# Notification_area.net
KiCad netlist of a schematic drawn in EAGLE
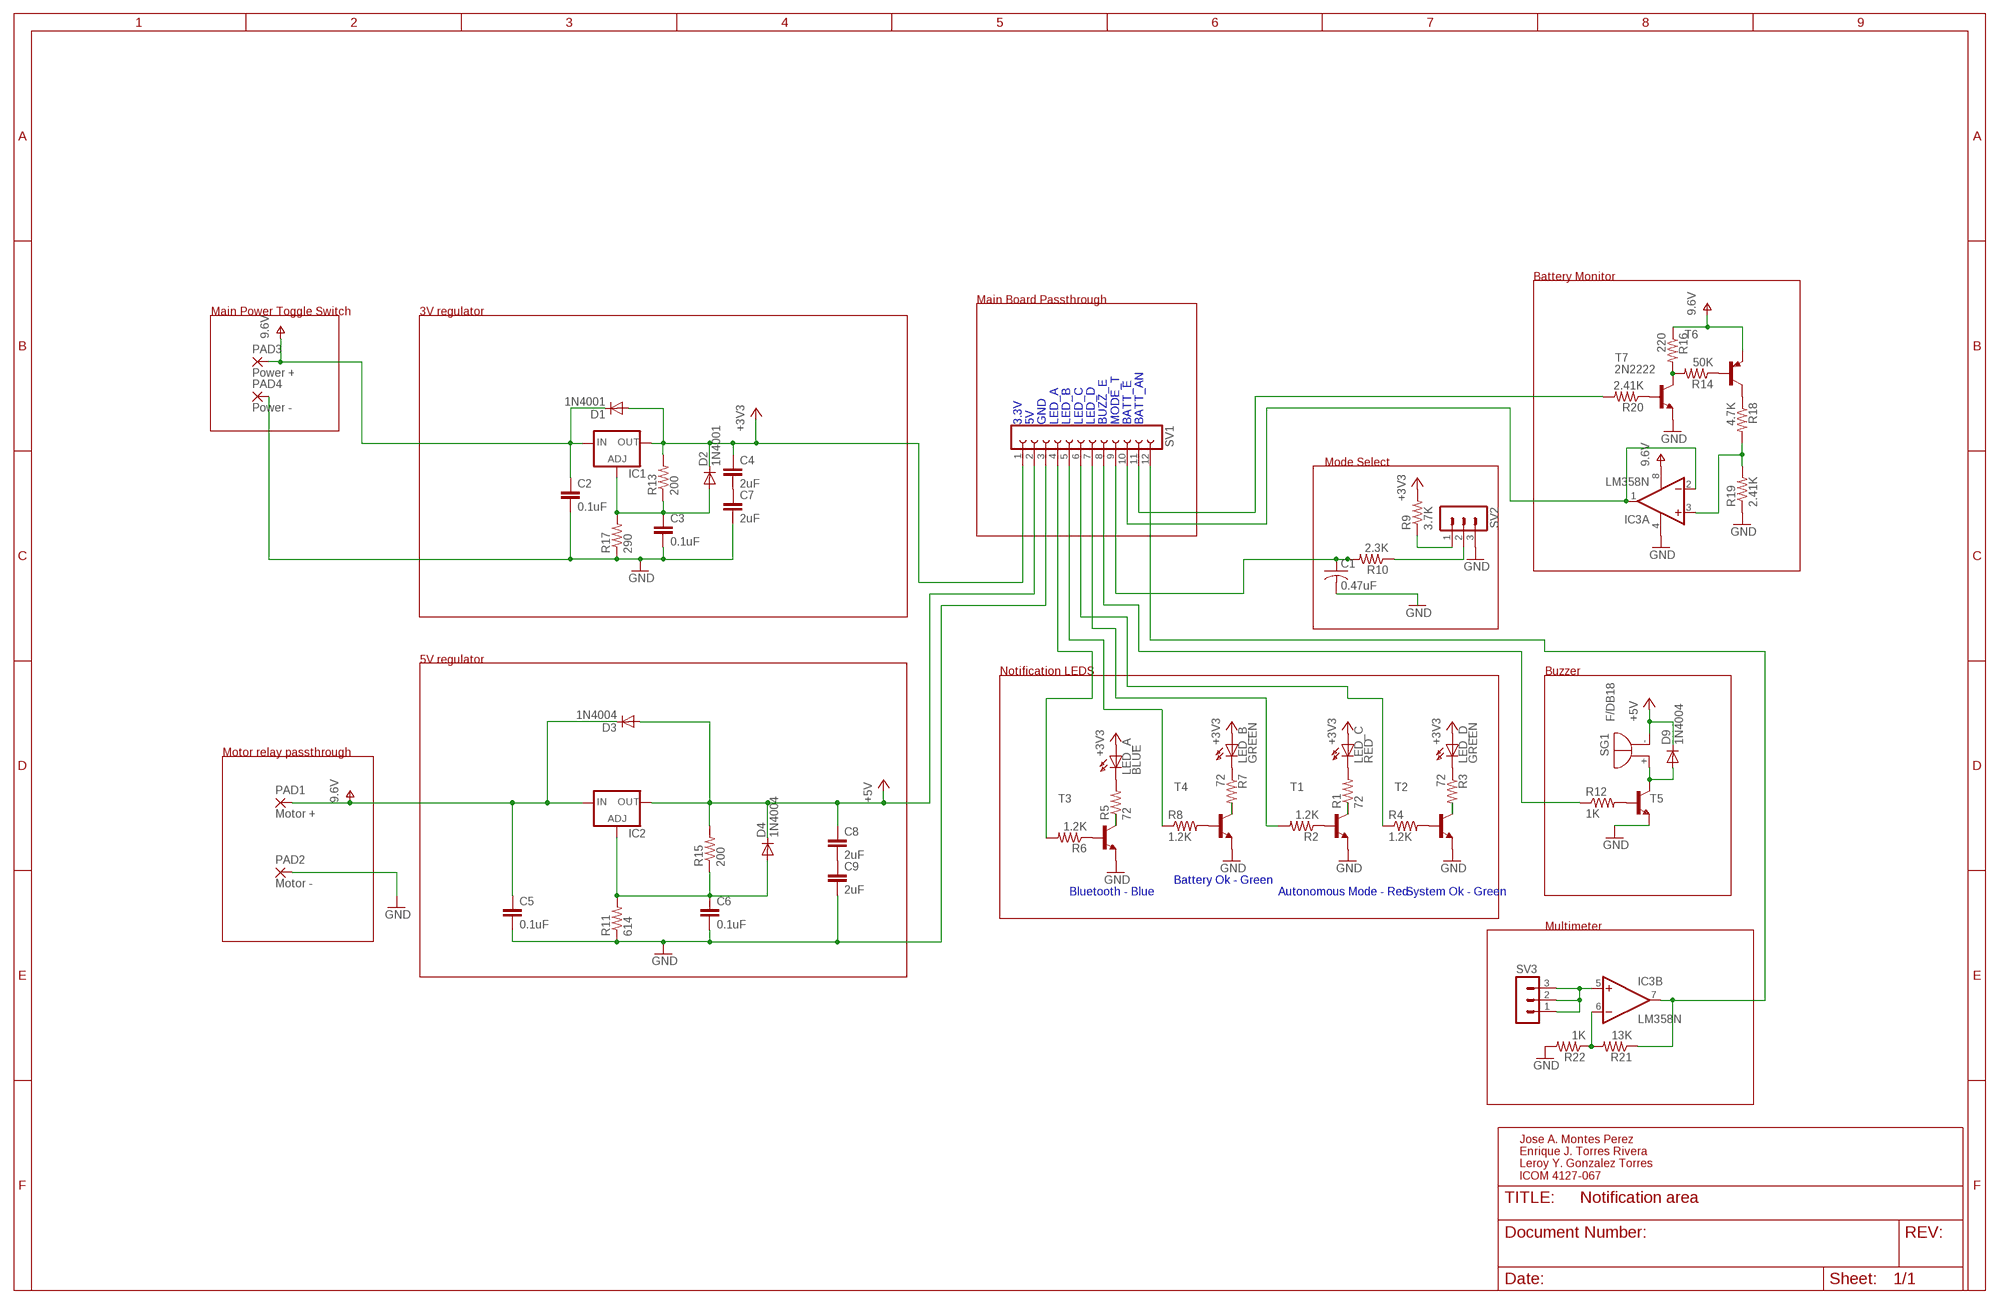
[diagram p0: schematic, sheet 1]

(export (version "E")
  (design (tool "Eeschema 10.0.6"))
  (components
    (comp (ref "C1")
      (value "0.47uF")
      (footprint "eagle-import:C025-030X050")
      (libsource (lib "eagle-import") (part "C-US025-030X050"))
    )
    (comp (ref "C2")
      (value "0.1uF")
      (footprint "eagle-import:C2.5-3")
      (libsource (lib "eagle-import") (part "C2,5-3"))
    )
    (comp (ref "C3")
      (value "0.1uF")
      (footprint "eagle-import:C2.5-3")
      (libsource (lib "eagle-import") (part "C2,5-3"))
    )
    (comp (ref "C4")
      (value "2uF")
      (footprint "eagle-import:C2.5-3")
      (libsource (lib "eagle-import") (part "C2,5-3"))
    )
    (comp (ref "C5")
      (value "0.1uF")
      (footprint "eagle-import:C2.5-3")
      (libsource (lib "eagle-import") (part "C2,5-3"))
    )
    (comp (ref "C6")
      (value "0.1uF")
      (footprint "eagle-import:C2.5-3")
      (libsource (lib "eagle-import") (part "C2,5-3"))
    )
    (comp (ref "C7")
      (value "2uF")
      (footprint "eagle-import:C2.5-3")
      (libsource (lib "eagle-import") (part "C2,5-3"))
    )
    (comp (ref "C8")
      (value "2uF")
      (footprint "eagle-import:C2.5-3")
      (libsource (lib "eagle-import") (part "C2,5-3"))
    )
    (comp (ref "C9")
      (value "2uF")
      (footprint "eagle-import:C2.5-3")
      (libsource (lib "eagle-import") (part "C2,5-3"))
    )
    (comp (ref "D1")
      (value "1N4001")
      (footprint "eagle-import:DO41-10")
      (libsource (lib "eagle-import") (part "1N4004"))
    )
    (comp (ref "D2")
      (value "1N4001")
      (footprint "eagle-import:DO41-10")
      (libsource (lib "eagle-import") (part "1N4004"))
    )
    (comp (ref "D3")
      (value "1N4004")
      (footprint "eagle-import:DO41-10")
      (libsource (lib "eagle-import") (part "1N4004"))
    )
    (comp (ref "D4")
      (value "1N4004")
      (footprint "eagle-import:DO41-10")
      (libsource (lib "eagle-import") (part "1N4004"))
    )
    (comp (ref "D9")
      (value "1N4004")
      (footprint "eagle-import:DO41-10")
      (libsource (lib "eagle-import") (part "1N4004"))
    )
    (comp (ref "IC1")
      (value "LM317TS")
      (footprint "eagle-import:317TS")
      (libsource (lib "eagle-import") (part "LM317TS"))
    )
    (comp (ref "IC2")
      (value "LM317TS")
      (footprint "eagle-import:317TS")
      (libsource (lib "eagle-import") (part "LM317TS"))
    )
    (comp (ref "IC3")
      (value "LM358N")
      (footprint "eagle-import:DIL08")
      (libsource (lib "eagle-import") (part "LM358N"))
    )
    (comp (ref "LED_A")
      (value "BLUE")
      (footprint "eagle-import:HLMP6")
      (fields (field (name "MF") "AGILENT TECHNOLOGIES") (field (name "MPN") "HLMP-6500"))
      (libsource (lib "eagle-import") (part "HLMP6"))
    )
    (comp (ref "LED_B")
      (value "GREEN")
      (footprint "eagle-import:HLMP6")
      (fields (field (name "MF") "AGILENT TECHNOLOGIES") (field (name "MPN") "HLMP-6500"))
      (libsource (lib "eagle-import") (part "HLMP6"))
    )
    (comp (ref "LED_C")
      (value "RED")
      (footprint "eagle-import:HLMP6")
      (fields (field (name "MF") "AGILENT TECHNOLOGIES") (field (name "MPN") "HLMP-6500"))
      (libsource (lib "eagle-import") (part "HLMP6"))
    )
    (comp (ref "LED_D")
      (value "GREEN")
      (footprint "eagle-import:HLMP6")
      (fields (field (name "MF") "AGILENT TECHNOLOGIES") (field (name "MPN") "HLMP-6500"))
      (libsource (lib "eagle-import") (part "HLMP6"))
    )
    (comp (ref "PAD1")
      (value "Motor +")
      (footprint "eagle-import:5-2,5")
      (libsource (lib "eagle-import") (part "WIREPADSMD5-2,5"))
    )
    (comp (ref "PAD2")
      (value "Motor -")
      (footprint "eagle-import:5-2,5")
      (libsource (lib "eagle-import") (part "WIREPADSMD5-2,5"))
    )
    (comp (ref "PAD3")
      (value "Power +")
      (footprint "eagle-import:5-2,5")
      (libsource (lib "eagle-import") (part "WIREPADSMD5-2,5"))
    )
    (comp (ref "PAD4")
      (value "Power -")
      (footprint "eagle-import:5-2,5")
      (libsource (lib "eagle-import") (part "WIREPADSMD5-2,5"))
    )
    (comp (ref "R1")
      (value "72")
      (footprint "eagle-import:0204_7")
      (libsource (lib "eagle-import") (part "R-US_0204/7"))
    )
    (comp (ref "R2")
      (value "1.2K")
      (footprint "eagle-import:0204_7")
      (libsource (lib "eagle-import") (part "R-US_0204/7"))
    )
    (comp (ref "R3")
      (value "72")
      (footprint "eagle-import:0204_7")
      (libsource (lib "eagle-import") (part "R-US_0204/7"))
    )
    (comp (ref "R4")
      (value "1.2K")
      (footprint "eagle-import:0204_7")
      (libsource (lib "eagle-import") (part "R-US_0204/7"))
    )
    (comp (ref "R5")
      (value "72")
      (footprint "eagle-import:0204_7")
      (libsource (lib "eagle-import") (part "R-US_0204/7"))
    )
    (comp (ref "R6")
      (value "1.2K")
      (footprint "eagle-import:0204_7")
      (libsource (lib "eagle-import") (part "R-US_0204/7"))
    )
    (comp (ref "R7")
      (value "72")
      (footprint "eagle-import:0204_7")
      (libsource (lib "eagle-import") (part "R-US_0204/7"))
    )
    (comp (ref "R8")
      (value "1.2K")
      (footprint "eagle-import:0204_7")
      (libsource (lib "eagle-import") (part "R-US_0204/7"))
    )
    (comp (ref "R9")
      (value "3.7K")
      (footprint "eagle-import:0204_7")
      (libsource (lib "eagle-import") (part "R-US_0204/7"))
    )
    (comp (ref "R10")
      (value "2.3K")
      (footprint "eagle-import:0204_7")
      (libsource (lib "eagle-import") (part "R-US_0204/7"))
    )
    (comp (ref "R11")
      (value "614")
      (footprint "eagle-import:0204_7")
      (libsource (lib "eagle-import") (part "R-US_0204/7"))
    )
    (comp (ref "R12")
      (value "1K")
      (footprint "eagle-import:0207_7")
      (libsource (lib "eagle-import") (part "R-US_0207/7"))
    )
    (comp (ref "R13")
      (value "200")
      (footprint "eagle-import:0204_7")
      (libsource (lib "eagle-import") (part "R-US_0204/7"))
    )
    (comp (ref "R14")
      (value "50K")
      (footprint "eagle-import:0204_7")
      (libsource (lib "eagle-import") (part "R-US_0204/7"))
    )
    (comp (ref "R15")
      (value "200")
      (footprint "eagle-import:0204_7")
      (libsource (lib "eagle-import") (part "R-US_0204/7"))
    )
    (comp (ref "R16")
      (value "220")
      (footprint "eagle-import:0204_7")
      (libsource (lib "eagle-import") (part "R-US_0204/7"))
    )
    (comp (ref "R17")
      (value "290")
      (footprint "eagle-import:0204_7")
      (libsource (lib "eagle-import") (part "R-US_0204/7"))
    )
    (comp (ref "R18")
      (value "4.7K")
      (footprint "eagle-import:0204_7")
      (libsource (lib "eagle-import") (part "R-US_0204/7"))
    )
    (comp (ref "R19")
      (value "2.41K")
      (footprint "eagle-import:0204_7")
      (libsource (lib "eagle-import") (part "R-US_0204/7"))
    )
    (comp (ref "R20")
      (value "2.41K")
      (footprint "eagle-import:0204_7")
      (libsource (lib "eagle-import") (part "R-US_0204/7"))
    )
    (comp (ref "R21")
      (value "13K")
      (footprint "eagle-import:0204_7")
      (libsource (lib "eagle-import") (part "R-US_0204/7"))
    )
    (comp (ref "R22")
      (value "1K")
      (footprint "eagle-import:0204_7")
      (libsource (lib "eagle-import") (part "R-US_0204/7"))
    )
    (comp (ref "SG1")
      (value "F/DB18")
      (footprint "eagle-import:F_DB18")
      (libsource (lib "eagle-import") (part "F/DB18"))
    )
    (comp (ref "SV1")
      (value "FE12-1")
      (footprint "eagle-import:FE12")
      (libsource (lib "eagle-import") (part "FE12-1"))
    )
    (comp (ref "SV2")
      (value "MA03-1")
      (footprint "eagle-import:MA03-1")
      (libsource (lib "eagle-import") (part "MA03-1"))
    )
    (comp (ref "SV3")
      (value "MA03-1")
      (footprint "eagle-import:MA03-1")
      (libsource (lib "eagle-import") (part "MA03-1"))
    )
    (comp (ref "T1")
      (value "2N2222-NPN-TO92-EBC")
      (footprint "eagle-import:TO92-EBC")
      (libsource (lib "eagle-import") (part "-NPN-TO92-EBC2N2222"))
    )
    (comp (ref "T2")
      (value "2N2222-NPN-TO92-EBC")
      (footprint "eagle-import:TO92-EBC")
      (libsource (lib "eagle-import") (part "-NPN-TO92-EBC2N2222"))
    )
    (comp (ref "T3")
      (value "2N2222-NPN-TO92-EBC")
      (footprint "eagle-import:TO92-EBC")
      (libsource (lib "eagle-import") (part "-NPN-TO92-EBC2N2222"))
    )
    (comp (ref "T4")
      (value "2N2222-NPN-TO92-EBC")
      (footprint "eagle-import:TO92-EBC")
      (libsource (lib "eagle-import") (part "-NPN-TO92-EBC2N2222"))
    )
    (comp (ref "T5")
      (value "2N2222-NPN-TO92-EBC")
      (footprint "eagle-import:TO92-EBC")
      (libsource (lib "eagle-import") (part "-NPN-TO92-EBC2N2222"))
    )
    (comp (ref "T6")
      (value "2N3906-PNP-TO92-EBC")
      (footprint "eagle-import:TO92-EBC")
      (libsource (lib "eagle-import") (part "-PNP-TO92-EBC2N3906"))
    )
    (comp (ref "T7")
      (value "2N2222")
      (footprint "eagle-import:TO18")
      (libsource (lib "eagle-import") (part "2N2222"))
    )
  )
  (nets
    (net (code "1") (name "+3V3") (class "Default")
      (node (ref "C4") (pin "1") (pinfunction "1_1") (pintype "passive"))
      (node (ref "D1") (pin "A") (pinfunction "A_A") (pintype "passive"))
      (node (ref "D2") (pin "C") (pinfunction "C_C") (pintype "passive"))
      (node (ref "IC1") (pin "2") (pinfunction "OUT_2") (pintype "passive"))
      (node (ref "LED_A") (pin "A") (pinfunction "A_A") (pintype "passive"))
      (node (ref "LED_B") (pin "A") (pinfunction "A_A") (pintype "passive"))
      (node (ref "LED_C") (pin "A") (pinfunction "A_A") (pintype "passive"))
      (node (ref "LED_D") (pin "A") (pinfunction "A_A") (pintype "passive"))
      (node (ref "R13") (pin "2") (pinfunction "2_2") (pintype "passive"))
      (node (ref "R9") (pin "2") (pinfunction "2_2") (pintype "passive"))
      (node (ref "SV1") (pin "1") (pinfunction "1_1") (pintype "passive"))
    )
    (net (code "2") (name "+5V") (class "Default")
      (node (ref "C8") (pin "1") (pinfunction "1_1") (pintype "passive"))
      (node (ref "D3") (pin "A") (pinfunction "A_A") (pintype "passive"))
      (node (ref "D4") (pin "C") (pinfunction "C_C") (pintype "passive"))
      (node (ref "D9") (pin "C") (pinfunction "C_C") (pintype "passive"))
      (node (ref "IC2") (pin "2") (pinfunction "OUT_2") (pintype "passive"))
      (node (ref "R15") (pin "2") (pinfunction "2_2") (pintype "passive"))
      (node (ref "SG1") (pin "-") (pinfunction "-_-") (pintype "passive"))
      (node (ref "SV1") (pin "2") (pinfunction "2_2") (pintype "passive"))
    )
    (net (code "3") (name "9.6V") (class "Default")
      (node (ref "C2") (pin "1") (pinfunction "1_1") (pintype "passive"))
      (node (ref "C5") (pin "1") (pinfunction "1_1") (pintype "passive"))
      (node (ref "D1") (pin "C") (pinfunction "C_C") (pintype "passive"))
      (node (ref "D3") (pin "C") (pinfunction "C_C") (pintype "passive"))
      (node (ref "IC1") (pin "3") (pinfunction "IN_3") (pintype "input"))
      (node (ref "IC2") (pin "3") (pinfunction "IN_3") (pintype "input"))
      (node (ref "IC3") (pin "8") (pinfunction "V+_8") (pintype "power_in"))
      (node (ref "PAD1") (pin "1") (pinfunction "P_1") (pintype "passive"))
      (node (ref "PAD3") (pin "1") (pinfunction "P_1") (pintype "passive"))
      (node (ref "R16") (pin "1") (pinfunction "1_1") (pintype "passive"))
      (node (ref "T6") (pin "E") (pinfunction "E_E") (pintype "passive"))
    )
    (net (code "4") (name "GND") (class "Default")
      (node (ref "C1") (pin "2") (pinfunction "2_2") (pintype "passive"))
      (node (ref "C2") (pin "2") (pinfunction "2_2") (pintype "passive"))
      (node (ref "C3") (pin "2") (pinfunction "2_2") (pintype "passive"))
      (node (ref "C5") (pin "2") (pinfunction "2_2") (pintype "passive"))
      (node (ref "C6") (pin "2") (pinfunction "2_2") (pintype "passive"))
      (node (ref "C7") (pin "2") (pinfunction "2_2") (pintype "passive"))
      (node (ref "C9") (pin "2") (pinfunction "2_2") (pintype "passive"))
      (node (ref "IC3") (pin "4") (pinfunction "V-_4") (pintype "power_in"))
      (node (ref "PAD2") (pin "1") (pinfunction "P_1") (pintype "passive"))
      (node (ref "PAD4") (pin "1") (pinfunction "P_1") (pintype "passive"))
      (node (ref "R11") (pin "1") (pinfunction "1_1") (pintype "passive"))
      (node (ref "R17") (pin "1") (pinfunction "1_1") (pintype "passive"))
      (node (ref "R19") (pin "1") (pinfunction "1_1") (pintype "passive"))
      (node (ref "R22") (pin "2") (pinfunction "2_2") (pintype "passive"))
      (node (ref "SV1") (pin "3") (pinfunction "3_3") (pintype "passive"))
      (node (ref "SV2") (pin "3") (pinfunction "3_3") (pintype "passive"))
      (node (ref "T1") (pin "E") (pinfunction "E_E") (pintype "passive"))
      (node (ref "T2") (pin "E") (pinfunction "E_E") (pintype "passive"))
      (node (ref "T3") (pin "E") (pinfunction "E_E") (pintype "passive"))
      (node (ref "T4") (pin "E") (pinfunction "E_E") (pintype "passive"))
      (node (ref "T5") (pin "E") (pinfunction "E_E") (pintype "passive"))
      (node (ref "T7") (pin "1") (pinfunction "E_1") (pintype "passive"))
    )
    (net (code "5") (name "Net-(C1-Pad1)") (class "Default")
      (node (ref "C1") (pin "1") (pinfunction "1_1") (pintype "passive"))
      (node (ref "R10") (pin "2") (pinfunction "2_2") (pintype "passive"))
      (node (ref "SV1") (pin "9") (pinfunction "9_9") (pintype "passive"))
    )
    (net (code "6") (name "Net-(C4-Pad2)") (class "Default")
      (node (ref "C4") (pin "2") (pinfunction "2_2") (pintype "passive"))
      (node (ref "C7") (pin "1") (pinfunction "1_1") (pintype "passive"))
    )
    (net (code "7") (name "Net-(C8-Pad2)") (class "Default")
      (node (ref "C8") (pin "2") (pinfunction "2_2") (pintype "passive"))
      (node (ref "C9") (pin "1") (pinfunction "1_1") (pintype "passive"))
    )
    (net (code "8") (name "Net-(D9-PadA)") (class "Default")
      (node (ref "D9") (pin "A") (pinfunction "A_A") (pintype "passive"))
      (node (ref "SG1") (pin "+") (pinfunction "+_+") (pintype "passive"))
      (node (ref "T5") (pin "C") (pinfunction "C_C") (pintype "passive"))
    )
    (net (code "9") (name "Net-(IC1-ADJ)") (class "Default")
      (node (ref "C3") (pin "1") (pinfunction "1_1") (pintype "passive"))
      (node (ref "D2") (pin "A") (pinfunction "A_A") (pintype "passive"))
      (node (ref "IC1") (pin "1") (pinfunction "ADJ_1") (pintype "input"))
      (node (ref "R13") (pin "1") (pinfunction "1_1") (pintype "passive"))
      (node (ref "R17") (pin "2") (pinfunction "2_2") (pintype "passive"))
    )
    (net (code "10") (name "Net-(IC2-ADJ)") (class "Default")
      (node (ref "C6") (pin "1") (pinfunction "1_1") (pintype "passive"))
      (node (ref "D4") (pin "A") (pinfunction "A_A") (pintype "passive"))
      (node (ref "IC2") (pin "1") (pinfunction "ADJ_1") (pintype "input"))
      (node (ref "R11") (pin "2") (pinfunction "2_2") (pintype "passive"))
      (node (ref "R15") (pin "1") (pinfunction "1_1") (pintype "passive"))
    )
    (net (code "11") (name "Net-(IC3A-+IN)") (class "Default")
      (node (ref "IC3") (pin "3") (pinfunction "+IN_3") (pintype "input"))
      (node (ref "R18") (pin "2") (pinfunction "2_2") (pintype "passive"))
      (node (ref "R19") (pin "2") (pinfunction "2_2") (pintype "passive"))
    )
    (net (code "12") (name "Net-(IC3A--IN)") (class "Default")
      (node (ref "IC3") (pin "1") (pinfunction "OUT_1") (pintype "output"))
      (node (ref "IC3") (pin "2") (pinfunction "-IN_2") (pintype "input"))
      (node (ref "SV1") (pin "10") (pinfunction "10_10") (pintype "passive"))
    )
    (net (code "13") (name "Net-(IC3B-+IN)") (class "Default")
      (node (ref "IC3") (pin "5") (pinfunction "+IN_5") (pintype "input"))
      (node (ref "SV3") (pin "1") (pinfunction "1_1") (pintype "passive"))
      (node (ref "SV3") (pin "2") (pinfunction "2_2") (pintype "passive"))
      (node (ref "SV3") (pin "3") (pinfunction "3_3") (pintype "passive"))
    )
    (net (code "14") (name "Net-(IC3B--IN)") (class "Default")
      (node (ref "IC3") (pin "6") (pinfunction "-IN_6") (pintype "input"))
      (node (ref "R21") (pin "2") (pinfunction "2_2") (pintype "passive"))
      (node (ref "R22") (pin "1") (pinfunction "1_1") (pintype "passive"))
    )
    (net (code "15") (name "Net-(IC3B-OUT)") (class "Default")
      (node (ref "IC3") (pin "7") (pinfunction "OUT_7") (pintype "output"))
      (node (ref "R21") (pin "1") (pinfunction "1_1") (pintype "passive"))
      (node (ref "SV1") (pin "12") (pinfunction "12_12") (pintype "passive"))
    )
    (net (code "16") (name "Net-(LED_A-PadK)") (class "Default")
      (node (ref "LED_A") (pin "K") (pinfunction "K_K") (pintype "passive"))
      (node (ref "R5") (pin "2") (pinfunction "2_2") (pintype "passive"))
    )
    (net (code "17") (name "Net-(LED_B-PadK)") (class "Default")
      (node (ref "LED_B") (pin "K") (pinfunction "K_K") (pintype "passive"))
      (node (ref "R7") (pin "1") (pinfunction "1_1") (pintype "passive"))
    )
    (net (code "18") (name "Net-(LED_C-PadK)") (class "Default")
      (node (ref "LED_C") (pin "K") (pinfunction "K_K") (pintype "passive"))
      (node (ref "R1") (pin "2") (pinfunction "2_2") (pintype "passive"))
    )
    (net (code "19") (name "Net-(LED_D-PadK)") (class "Default")
      (node (ref "LED_D") (pin "K") (pinfunction "K_K") (pintype "passive"))
      (node (ref "R3") (pin "1") (pinfunction "1_1") (pintype "passive"))
    )
    (net (code "20") (name "Net-(R1-Pad1)") (class "Default")
      (node (ref "R1") (pin "1") (pinfunction "1_1") (pintype "passive"))
      (node (ref "T1") (pin "C") (pinfunction "C_C") (pintype "passive"))
    )
    (net (code "21") (name "Net-(R2-Pad1)") (class "Default")
      (node (ref "R2") (pin "1") (pinfunction "1_1") (pintype "passive"))
      (node (ref "T1") (pin "B") (pinfunction "B_B") (pintype "passive"))
    )
    (net (code "22") (name "Net-(R2-Pad2)") (class "Default")
      (node (ref "R2") (pin "2") (pinfunction "2_2") (pintype "passive"))
      (node (ref "SV1") (pin "7") (pinfunction "7_7") (pintype "passive"))
    )
    (net (code "23") (name "Net-(R3-Pad2)") (class "Default")
      (node (ref "R3") (pin "2") (pinfunction "2_2") (pintype "passive"))
      (node (ref "T2") (pin "C") (pinfunction "C_C") (pintype "passive"))
    )
    (net (code "24") (name "Net-(R4-Pad1)") (class "Default")
      (node (ref "R4") (pin "1") (pinfunction "1_1") (pintype "passive"))
      (node (ref "SV1") (pin "6") (pinfunction "6_6") (pintype "passive"))
    )
    (net (code "25") (name "Net-(R4-Pad2)") (class "Default")
      (node (ref "R4") (pin "2") (pinfunction "2_2") (pintype "passive"))
      (node (ref "T2") (pin "B") (pinfunction "B_B") (pintype "passive"))
    )
    (net (code "26") (name "Net-(R5-Pad1)") (class "Default")
      (node (ref "R5") (pin "1") (pinfunction "1_1") (pintype "passive"))
      (node (ref "T3") (pin "C") (pinfunction "C_C") (pintype "passive"))
    )
    (net (code "27") (name "Net-(R6-Pad1)") (class "Default")
      (node (ref "R6") (pin "1") (pinfunction "1_1") (pintype "passive"))
      (node (ref "T3") (pin "B") (pinfunction "B_B") (pintype "passive"))
    )
    (net (code "28") (name "Net-(R6-Pad2)") (class "Default")
      (node (ref "R6") (pin "2") (pinfunction "2_2") (pintype "passive"))
      (node (ref "SV1") (pin "4") (pinfunction "4_4") (pintype "passive"))
    )
    (net (code "29") (name "Net-(R7-Pad2)") (class "Default")
      (node (ref "R7") (pin "2") (pinfunction "2_2") (pintype "passive"))
      (node (ref "T4") (pin "C") (pinfunction "C_C") (pintype "passive"))
    )
    (net (code "30") (name "Net-(R8-Pad1)") (class "Default")
      (node (ref "R8") (pin "1") (pinfunction "1_1") (pintype "passive"))
      (node (ref "SV1") (pin "5") (pinfunction "5_5") (pintype "passive"))
    )
    (net (code "31") (name "Net-(R8-Pad2)") (class "Default")
      (node (ref "R8") (pin "2") (pinfunction "2_2") (pintype "passive"))
      (node (ref "T4") (pin "B") (pinfunction "B_B") (pintype "passive"))
    )
    (net (code "32") (name "Net-(R9-Pad1)") (class "Default")
      (node (ref "R9") (pin "1") (pinfunction "1_1") (pintype "passive"))
      (node (ref "SV2") (pin "1") (pinfunction "1_1") (pintype "passive"))
    )
    (net (code "33") (name "Net-(R10-Pad1)") (class "Default")
      (node (ref "R10") (pin "1") (pinfunction "1_1") (pintype "passive"))
      (node (ref "SV2") (pin "2") (pinfunction "2_2") (pintype "passive"))
    )
    (net (code "34") (name "Net-(R12-Pad1)") (class "Default")
      (node (ref "R12") (pin "1") (pinfunction "1_1") (pintype "passive"))
      (node (ref "SV1") (pin "8") (pinfunction "8_8") (pintype "passive"))
    )
    (net (code "35") (name "Net-(R12-Pad2)") (class "Default")
      (node (ref "R12") (pin "2") (pinfunction "2_2") (pintype "passive"))
      (node (ref "T5") (pin "B") (pinfunction "B_B") (pintype "passive"))
    )
    (net (code "36") (name "Net-(R14-Pad1)") (class "Default")
      (node (ref "R14") (pin "1") (pinfunction "1_1") (pintype "passive"))
      (node (ref "T6") (pin "B") (pinfunction "B_B") (pintype "passive"))
    )
    (net (code "37") (name "Net-(R18-Pad1)") (class "Default")
      (node (ref "R18") (pin "1") (pinfunction "1_1") (pintype "passive"))
      (node (ref "T6") (pin "C") (pinfunction "C_C") (pintype "passive"))
    )
    (net (code "38") (name "Net-(R20-Pad2)") (class "Default")
      (node (ref "R20") (pin "2") (pinfunction "2_2") (pintype "passive"))
      (node (ref "SV1") (pin "11") (pinfunction "11_11") (pintype "passive"))
    )
    (net (code "39") (name "Net-(T7-B)") (class "Default")
      (node (ref "R20") (pin "1") (pinfunction "1_1") (pintype "passive"))
      (node (ref "T7") (pin "2") (pinfunction "B_2") (pintype "passive"))
    )
    (net (code "40") (name "Net-(T7-C)") (class "Default")
      (node (ref "R14") (pin "2") (pinfunction "2_2") (pintype "passive"))
      (node (ref "R16") (pin "2") (pinfunction "2_2") (pintype "passive"))
      (node (ref "T7") (pin "3") (pinfunction "C_3") (pintype "passive"))
    )
  )
)
